# coulomb_counter.net
KiCad netlist of a schematic drawn in EAGLE
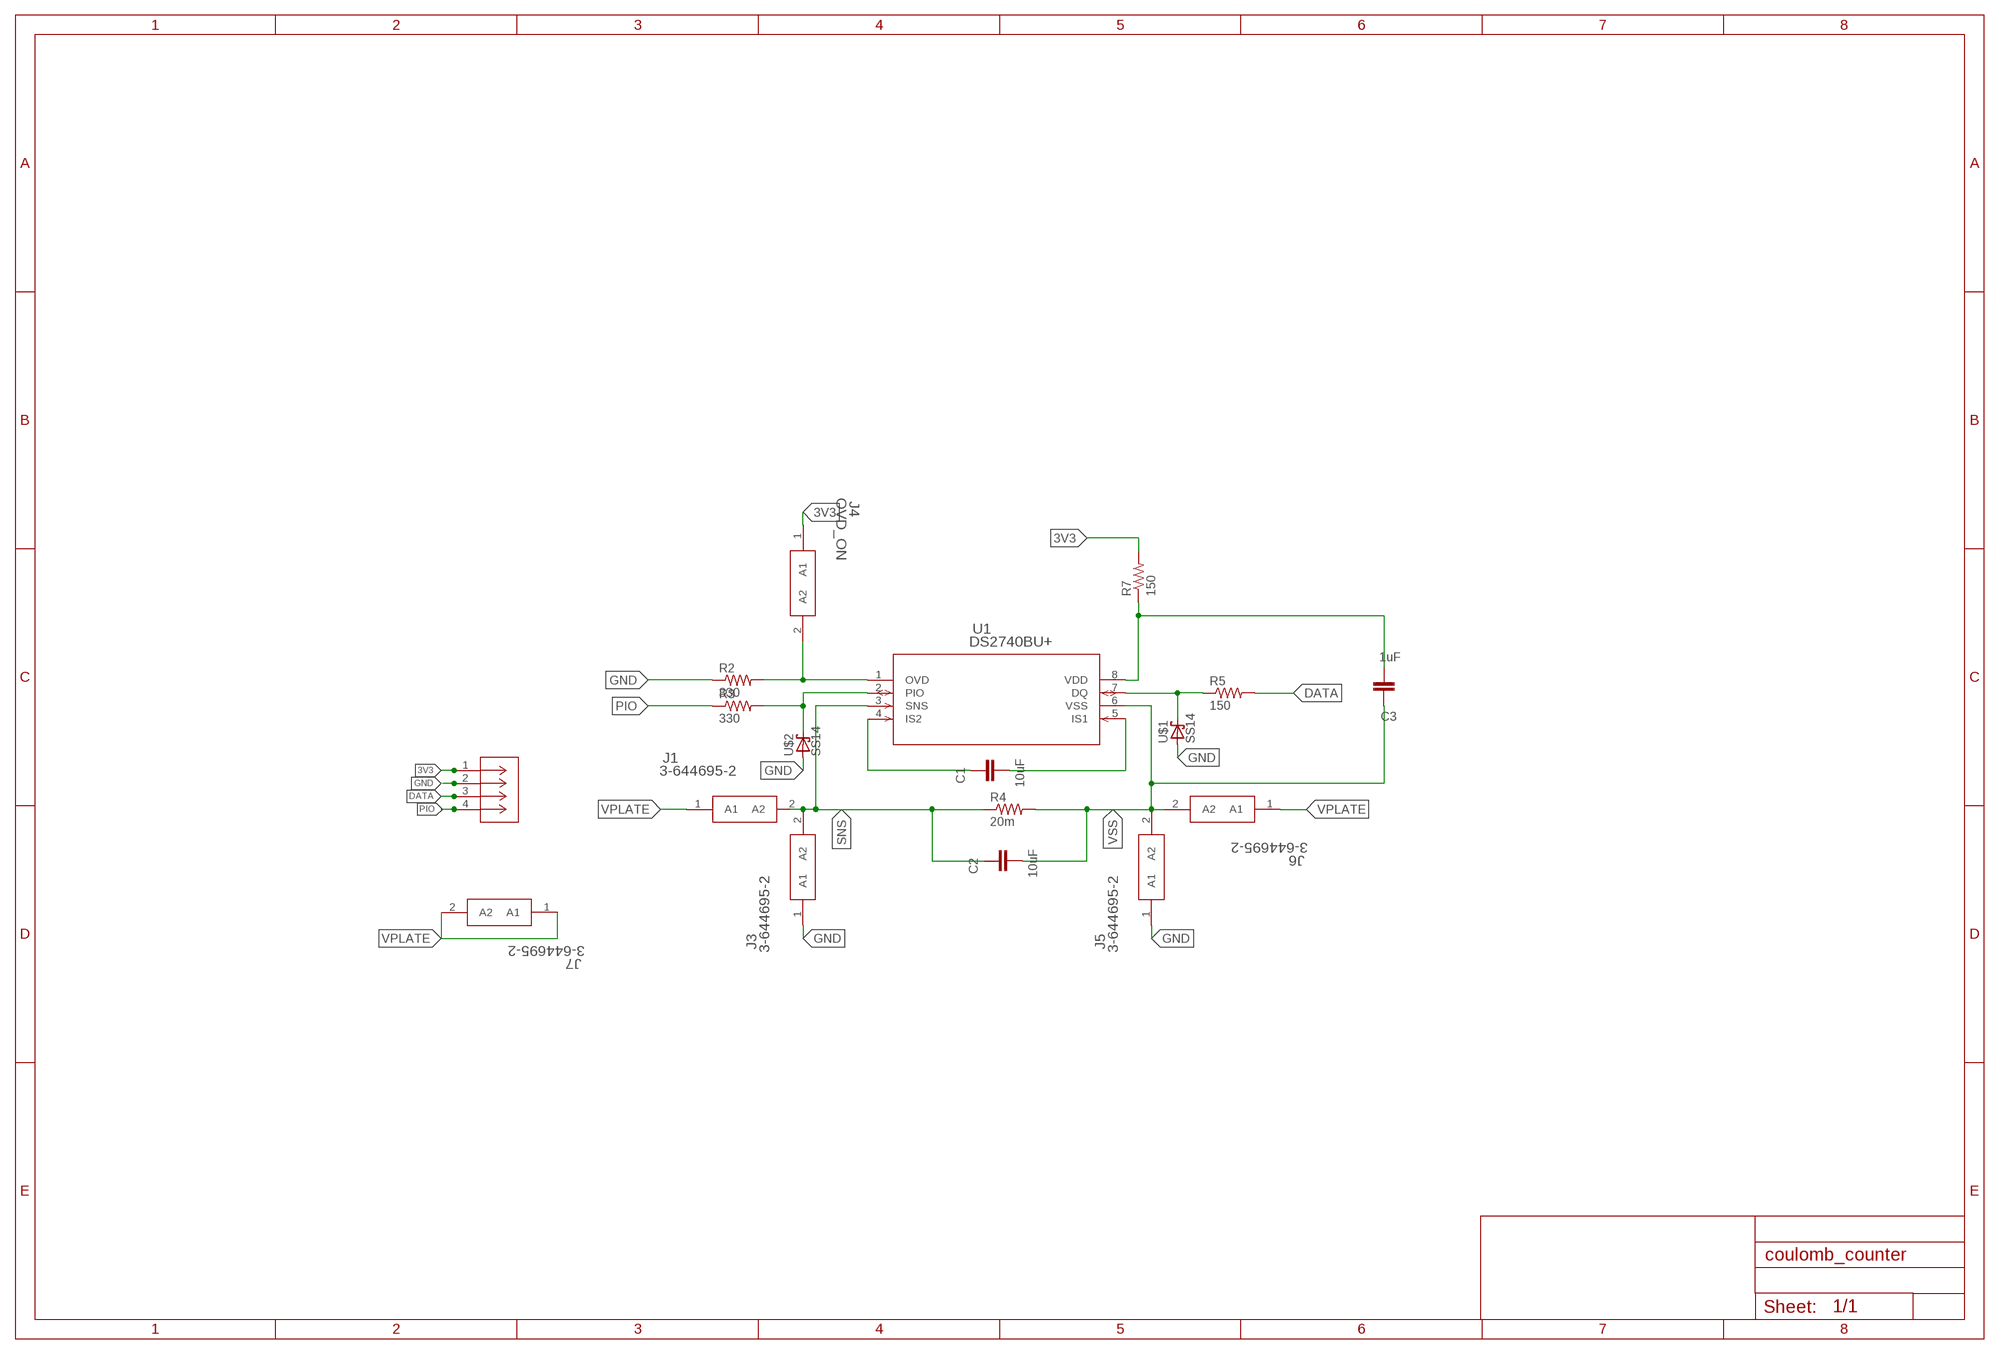
[diagram p0: schematic, sheet 1]

(export (version "E")
  (design (tool "Eeschema 10.0.6"))
  (components
    (comp (ref "C1")
      (value "10uF")
      (footprint "eagle-import:CAP_1206")
      (fields
        (field (name "DIGIKEY_PART_NUMBER") "GRM31CR60J107ME39L")
        (field (name "MANUFACTURER") "Murata Electronics North America")
        (field (name "CREATED_BY") "PCBLayout.com")
      )
      (libsource (lib "eagle-import") (part "GRM31CR60J107ME39L"))
    )
    (comp (ref "C2")
      (value "10uF")
      (footprint "eagle-import:CAP_1206")
      (fields
        (field (name "DIGIKEY_PART_NUMBER") "GRM31CR60J107ME39L")
        (field (name "MANUFACTURER") "Murata Electronics North America")
        (field (name "CREATED_BY") "PCBLayout.com")
      )
      (libsource (lib "eagle-import") (part "GRM31CR60J107ME39L"))
    )
    (comp (ref "C3")
      (value "1uF")
      (footprint "eagle-import:CAP_1206")
      (fields
        (field (name "DIGIKEY_PART_NUMBER") "GRM31CR60J107ME39L")
        (field (name "MANUFACTURER") "Murata Electronics North America")
        (field (name "CREATED_BY") "PCBLayout.com")
      )
      (libsource (lib "eagle-import") (part "GRM31CR60J107ME39L"))
    )
    (comp (ref "J1")
      (value "3-644695-2")
      (footprint "eagle-import:3-644695-2_TYC")
      (libsource (lib "eagle-import") (part "3-644695-2"))
    )
    (comp (ref "J2")
      (value "1935187")
      (footprint "eagle-import:CONN_1935187_PXC")
      (fields (field (name "COPYRIGHT") "Copyright (C) 2018 Accelerated Designs. All rights reserved"))
      (libsource (lib "eagle-import") (part "1935187"))
    )
    (comp (ref "J3")
      (value "3-644695-2")
      (footprint "eagle-import:3-644695-2_TYC")
      (libsource (lib "eagle-import") (part "3-644695-2"))
    )
    (comp (ref "J4")
      (value "OVD_ON")
      (footprint "eagle-import:3-644695-2_TYC")
      (fields (field (name "MANUFACTURER_PART_NUMBER") "3-644695-2"))
      (libsource (lib "eagle-import") (part "3-644695-2"))
    )
    (comp (ref "J5")
      (value "3-644695-2")
      (footprint "eagle-import:3-644695-2_TYC")
      (libsource (lib "eagle-import") (part "3-644695-2"))
    )
    (comp (ref "J6")
      (value "3-644695-2")
      (footprint "eagle-import:3-644695-2_TYC")
      (libsource (lib "eagle-import") (part "3-644695-2"))
    )
    (comp (ref "J7")
      (value "3-644695-2")
      (footprint "eagle-import:3-644695-2_TYC")
      (libsource (lib "eagle-import") (part "3-644695-2"))
    )
    (comp (ref "R2")
      (value "330")
      (footprint "eagle-import:RES_1206")
      (fields
        (field (name "DIGIKEY_PART_NUMBER") "P0.0ETR-ND")
        (field (name "MANUFACTURER") "Panasonic Electronic Components")
        (field (name "MPN") "ERJ-8GEY0R00V")
        (field (name "CREATED_BY") "PCBLayout.com")
      )
      (libsource (lib "eagle-import") (part "ERJ-8GEY0R00V"))
    )
    (comp (ref "R3")
      (value "330")
      (footprint "eagle-import:RES_1206")
      (fields
        (field (name "DIGIKEY_PART_NUMBER") "P0.0ETR-ND")
        (field (name "MANUFACTURER") "Panasonic Electronic Components")
        (field (name "MPN") "ERJ-8GEY0R00V")
        (field (name "CREATED_BY") "PCBLayout.com")
      )
      (libsource (lib "eagle-import") (part "ERJ-8GEY0R00V"))
    )
    (comp (ref "R4")
      (value "20m")
      (footprint "eagle-import:RES_1206")
      (fields
        (field (name "DIGIKEY_PART_NUMBER") "P0.0ETR-ND")
        (field (name "MANUFACTURER") "Panasonic Electronic Components")
        (field (name "MPN") "ERJ-8GEY0R00V")
        (field (name "CREATED_BY") "PCBLayout.com")
      )
      (libsource (lib "eagle-import") (part "ERJ-8GEY0R00V"))
    )
    (comp (ref "R5")
      (value "150")
      (footprint "eagle-import:RES_1206")
      (fields
        (field (name "DIGIKEY_PART_NUMBER") "P0.0ETR-ND")
        (field (name "MANUFACTURER") "Panasonic Electronic Components")
        (field (name "MPN") "ERJ-8GEY0R00V")
        (field (name "CREATED_BY") "PCBLayout.com")
      )
      (libsource (lib "eagle-import") (part "ERJ-8GEY0R00V"))
    )
    (comp (ref "R7")
      (value "150")
      (footprint "eagle-import:RES_1206")
      (fields
        (field (name "DIGIKEY_PART_NUMBER") "P0.0ETR-ND")
        (field (name "MANUFACTURER") "Panasonic Electronic Components")
        (field (name "MPN") "ERJ-8GEY0R00V")
        (field (name "CREATED_BY") "PCBLayout.com")
      )
      (libsource (lib "eagle-import") (part "ERJ-8GEY0R00V"))
    )
    (comp (ref "U$1")
      (value "SS14")
      (footprint "eagle-import:DO-214AC")
      (fields (field (name "MF") "ON Semiconductor"))
      (libsource (lib "eagle-import") (part "SS14"))
    )
    (comp (ref "U$2")
      (value "SS14")
      (footprint "eagle-import:DO-214AC")
      (fields (field (name "MF") "ON Semiconductor"))
      (libsource (lib "eagle-import") (part "SS14"))
    )
    (comp (ref "U1")
      (value "DS2740BU+")
      (footprint "eagle-import:21-0036K_MXM")
      (fields (field (name "MANUFACTURER_PART_NUMBER") "ds2740bu+"))
      (libsource (lib "eagle-import") (part "DS2740BU+"))
    )
  )
  (nets
    (net (code "1") (name "3V3") (class "Default")
      (node (ref "J2") (pin "1") (pinfunction "1_1") (pintype "passive"))
      (node (ref "J4") (pin "1") (pinfunction "A1_1") (pintype "passive"))
      (node (ref "R7") (pin "2") (pinfunction "2_2") (pintype "passive"))
    )
    (net (code "2") (name "DATA") (class "Default")
      (node (ref "J2") (pin "3") (pinfunction "3_3") (pintype "passive"))
      (node (ref "R5") (pin "2") (pinfunction "2_2") (pintype "passive"))
    )
    (net (code "3") (name "GND") (class "Default")
      (node (ref "J2") (pin "2") (pinfunction "2_2") (pintype "passive"))
      (node (ref "J3") (pin "1") (pinfunction "A1_1") (pintype "passive"))
      (node (ref "J5") (pin "1") (pinfunction "A1_1") (pintype "passive"))
      (node (ref "R2") (pin "1") (pinfunction "1_1") (pintype "passive"))
      (node (ref "U$1") (pin "A") (pinfunction "A_A") (pintype "passive"))
      (node (ref "U$2") (pin "A") (pinfunction "A_A") (pintype "passive"))
    )
    (net (code "4") (name "Net-(J4-A2)") (class "Default")
      (node (ref "J4") (pin "2") (pinfunction "A2_2") (pintype "passive"))
      (node (ref "R2") (pin "2") (pinfunction "2_2") (pintype "passive"))
      (node (ref "U1") (pin "1") (pinfunction "OVD_1") (pintype "passive"))
    )
    (net (code "5") (name "Net-(U1-DQ)") (class "Default")
      (node (ref "R5") (pin "1") (pinfunction "1_1") (pintype "passive"))
      (node (ref "U$1") (pin "C") (pinfunction "C_C") (pintype "passive"))
      (node (ref "U1") (pin "7") (pinfunction "DQ_7") (pintype "bidirectional"))
    )
    (net (code "6") (name "Net-(U1-IS1)") (class "Default")
      (node (ref "C1") (pin "2") (pinfunction "2_2") (pintype "passive"))
      (node (ref "U1") (pin "5") (pinfunction "IS1_5") (pintype "input"))
    )
    (net (code "7") (name "Net-(U1-IS2)") (class "Default")
      (node (ref "C1") (pin "1") (pinfunction "1_1") (pintype "passive"))
      (node (ref "U1") (pin "4") (pinfunction "IS2_4") (pintype "input"))
    )
    (net (code "8") (name "Net-(U1-PIO)") (class "Default")
      (node (ref "R3") (pin "2") (pinfunction "2_2") (pintype "passive"))
      (node (ref "U$2") (pin "C") (pinfunction "C_C") (pintype "passive"))
      (node (ref "U1") (pin "2") (pinfunction "PIO_2") (pintype "bidirectional"))
    )
    (net (code "9") (name "Net-(U1-VDD)") (class "Default")
      (node (ref "C3") (pin "2") (pinfunction "2_2") (pintype "passive"))
      (node (ref "R7") (pin "1") (pinfunction "1_1") (pintype "passive"))
      (node (ref "U1") (pin "8") (pinfunction "VDD_8") (pintype "power_in"))
    )
    (net (code "10") (name "PIO") (class "Default")
      (node (ref "J2") (pin "4") (pinfunction "4_4") (pintype "passive"))
      (node (ref "R3") (pin "1") (pinfunction "1_1") (pintype "passive"))
    )
    (net (code "11") (name "SNS") (class "Default")
      (node (ref "C2") (pin "1") (pinfunction "1_1") (pintype "passive"))
      (node (ref "J1") (pin "2") (pinfunction "A2_2") (pintype "passive"))
      (node (ref "J3") (pin "2") (pinfunction "A2_2") (pintype "passive"))
      (node (ref "R4") (pin "1") (pinfunction "1_1") (pintype "passive"))
      (node (ref "U1") (pin "3") (pinfunction "SNS_3") (pintype "input"))
    )
    (net (code "12") (name "VPLATE") (class "Default")
      (node (ref "J1") (pin "1") (pinfunction "A1_1") (pintype "passive"))
      (node (ref "J6") (pin "1") (pinfunction "A1_1") (pintype "passive"))
      (node (ref "J7") (pin "1") (pinfunction "A1_1") (pintype "passive"))
      (node (ref "J7") (pin "2") (pinfunction "A2_2") (pintype "passive"))
    )
    (net (code "13") (name "VSS") (class "Default")
      (node (ref "C2") (pin "2") (pinfunction "2_2") (pintype "passive"))
      (node (ref "C3") (pin "1") (pinfunction "1_1") (pintype "passive"))
      (node (ref "J5") (pin "2") (pinfunction "A2_2") (pintype "passive"))
      (node (ref "J6") (pin "2") (pinfunction "A2_2") (pintype "passive"))
      (node (ref "R4") (pin "2") (pinfunction "2_2") (pintype "passive"))
      (node (ref "U1") (pin "6") (pinfunction "VSS_6") (pintype "power_in"))
    )
  )
)
